# Teensy4_1V3.net
KiCad netlist of a schematic drawn in EAGLE
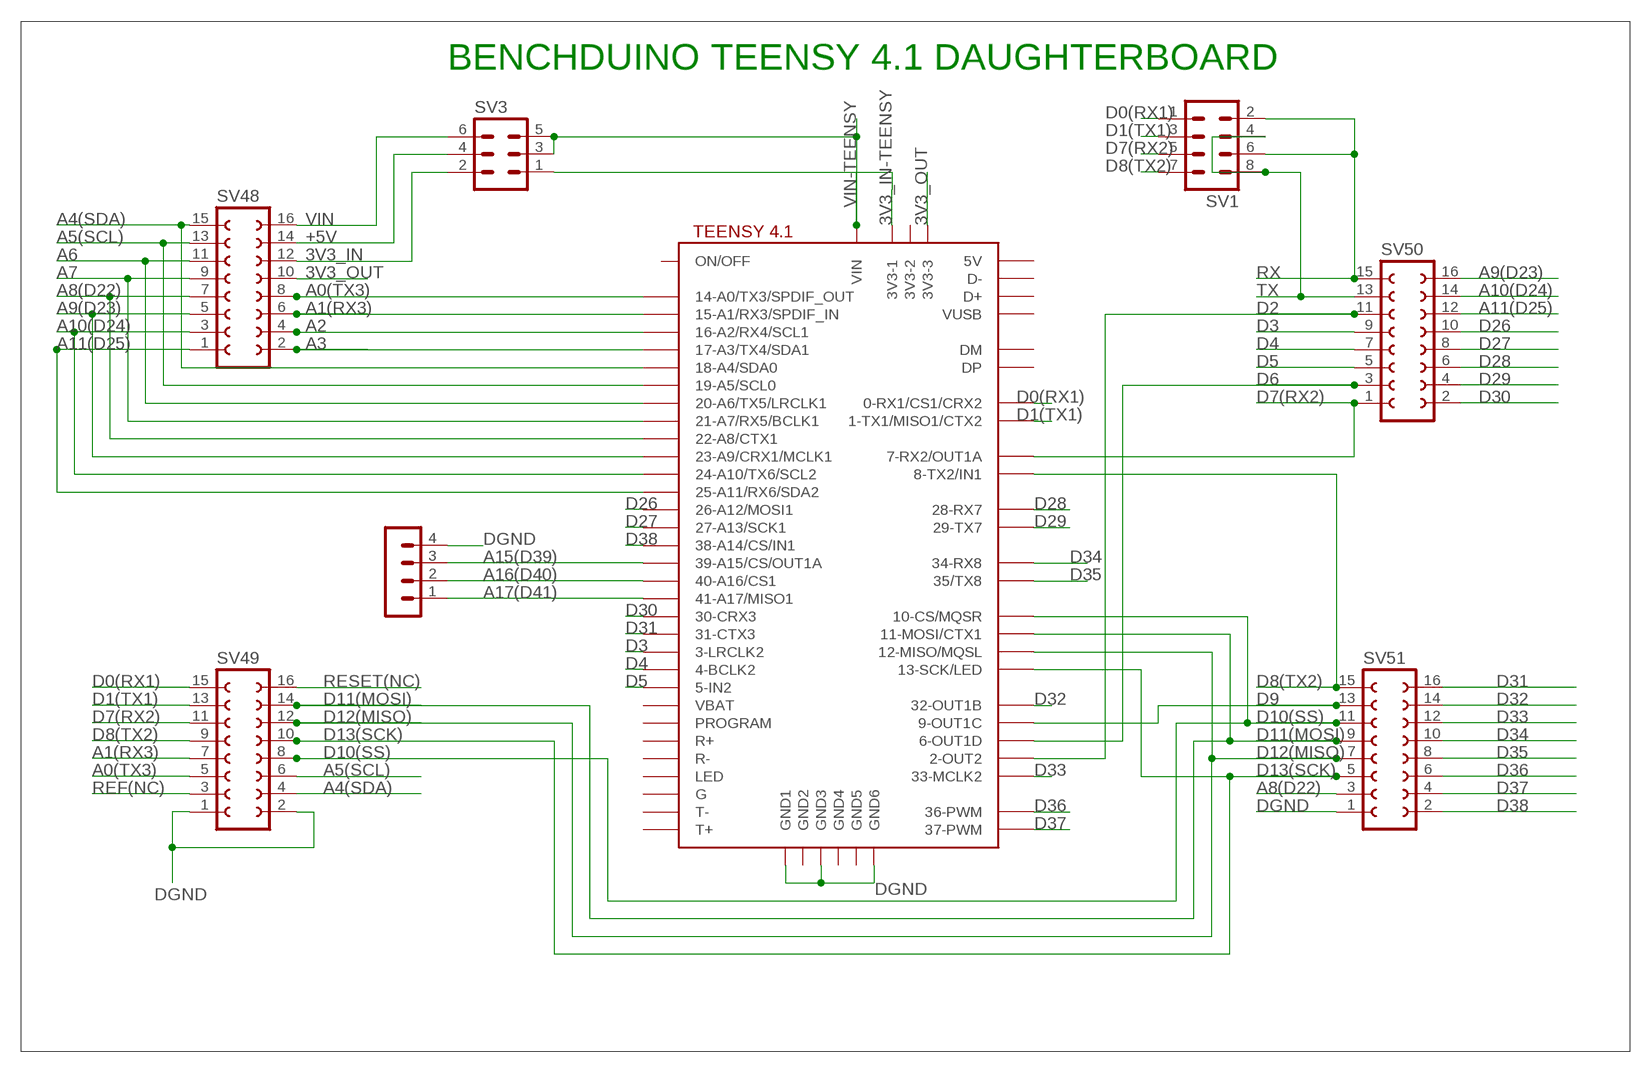
[diagram p0: schematic, sheet 1]

(export (version "E")
  (design (tool "Eeschema 10.0.6"))
  (components
    (comp (ref "SV1")
      (value "MA04-2")
      (footprint "eagle-import:MA04-2")
      (libsource (lib "eagle-import") (part "MA04-2"))
    )
    (comp (ref "SV3")
      (value "MA03-2")
      (footprint "eagle-import:MA03-2")
      (libsource (lib "eagle-import") (part "MA03-2"))
    )
    (comp (ref "SV4")
      (value "MA04-1")
      (footprint "eagle-import:MA04-1")
      (libsource (lib "eagle-import") (part "MA04-1"))
    )
    (comp (ref "SV48")
      (value "FE08-2")
      (footprint "eagle-import:FE08-2")
      (libsource (lib "eagle-import") (part "FE08-2"))
    )
    (comp (ref "SV49")
      (value "FE08-2")
      (footprint "eagle-import:FE08-2")
      (libsource (lib "eagle-import") (part "FE08-2"))
    )
    (comp (ref "SV50")
      (value "FE08-2")
      (footprint "eagle-import:FE08-2")
      (libsource (lib "eagle-import") (part "FE08-2"))
    )
    (comp (ref "SV51")
      (value "FE08-2")
      (footprint "eagle-import:FE08-2")
      (libsource (lib "eagle-import") (part "FE08-2"))
    )
    (comp (ref "U$1")
      (value "TEENSY41")
      (footprint "eagle-import:TEENSY41")
      (libsource (lib "eagle-import") (part "TEENSY41"))
    )
  )
  (nets
    (net (code "1") (name "+5V") (class "Default")
      (node (ref "SV3") (pin "4") (pinfunction "4_4") (pintype "passive"))
      (node (ref "SV48") (pin "14") (pinfunction "14_14") (pintype "passive"))
    )
    (net (code "2") (name "3V3_IN") (class "Default")
      (node (ref "SV3") (pin "2") (pinfunction "2_2") (pintype "passive"))
      (node (ref "SV48") (pin "12") (pinfunction "12_12") (pintype "passive"))
    )
    (net (code "3") (name "3V3_IN-TEENSY") (class "Default")
      (node (ref "SV3") (pin "1") (pinfunction "1_1") (pintype "passive"))
      (node (ref "U$1") (pin "3V3-1") (pinfunction "3V3-1_3V3-1") (pintype "bidirectional"))
    )
    (net (code "4") (name "3V3_OUT") (class "Default")
      (node (ref "SV48") (pin "10") (pinfunction "10_10") (pintype "passive"))
      (node (ref "U$1") (pin "3V3-3") (pinfunction "3V3-3_3V3-3") (pintype "bidirectional"))
    )
    (net (code "5") (name "A0(TX3)") (class "Default")
      (node (ref "SV48") (pin "8") (pinfunction "8_8") (pintype "passive"))
      (node (ref "SV49") (pin "5") (pinfunction "5_5") (pintype "passive"))
      (node (ref "U$1") (pin "14-A0/TX3/SPDIF_OUT") (pinfunction "14-A0/TX3/SPDIF_OUT_14-A0/TX3/SPDIF_OUT") (pintype "bidirectional"))
    )
    (net (code "6") (name "A1(RX3)") (class "Default")
      (node (ref "SV48") (pin "6") (pinfunction "6_6") (pintype "passive"))
      (node (ref "SV49") (pin "7") (pinfunction "7_7") (pintype "passive"))
      (node (ref "U$1") (pin "15-A1/RX3/SPDIF_IN") (pinfunction "15-A1/RX3/SPDIF_IN_15-A1/RX3/SPDIF_IN") (pintype "bidirectional"))
    )
    (net (code "7") (name "A2") (class "Default")
      (node (ref "SV48") (pin "4") (pinfunction "4_4") (pintype "passive"))
      (node (ref "U$1") (pin "16-A2/RX4/SCL1") (pinfunction "16-A2/RX4/SCL1_16-A2/RX4/SCL1") (pintype "bidirectional"))
    )
    (net (code "8") (name "A3") (class "Default")
      (node (ref "SV48") (pin "2") (pinfunction "2_2") (pintype "passive"))
      (node (ref "U$1") (pin "17-A3/TX4/SDA1") (pinfunction "17-A3/TX4/SDA1_17-A3/TX4/SDA1") (pintype "bidirectional"))
    )
    (net (code "9") (name "A4(SDA)") (class "Default")
      (node (ref "SV48") (pin "15") (pinfunction "15_15") (pintype "passive"))
      (node (ref "SV49") (pin "4") (pinfunction "4_4") (pintype "passive"))
      (node (ref "U$1") (pin "18-A4/SDA0") (pinfunction "18-A4/SDA0_18-A4/SDA0") (pintype "bidirectional"))
    )
    (net (code "10") (name "A5(SCL)") (class "Default")
      (node (ref "SV48") (pin "13") (pinfunction "13_13") (pintype "passive"))
      (node (ref "SV49") (pin "6") (pinfunction "6_6") (pintype "passive"))
      (node (ref "U$1") (pin "19-A5/SCL0") (pinfunction "19-A5/SCL0_19-A5/SCL0") (pintype "bidirectional"))
    )
    (net (code "11") (name "A6") (class "Default")
      (node (ref "SV48") (pin "11") (pinfunction "11_11") (pintype "passive"))
      (node (ref "U$1") (pin "20-A6/TX5/LRCLK1") (pinfunction "20-A6/TX5/LRCLK1_20-A6/TX5/LRCLK1") (pintype "bidirectional"))
    )
    (net (code "12") (name "A7") (class "Default")
      (node (ref "SV48") (pin "9") (pinfunction "9_9") (pintype "passive"))
      (node (ref "U$1") (pin "21-A7/RX5/BCLK1") (pinfunction "21-A7/RX5/BCLK1_21-A7/RX5/BCLK1") (pintype "bidirectional"))
    )
    (net (code "13") (name "A8(D22)") (class "Default")
      (node (ref "SV48") (pin "7") (pinfunction "7_7") (pintype "passive"))
      (node (ref "SV51") (pin "3") (pinfunction "3_3") (pintype "passive"))
      (node (ref "U$1") (pin "22-A8/CTX1") (pinfunction "22-A8/CTX1_22-A8/CTX1") (pintype "bidirectional"))
    )
    (net (code "14") (name "A9(D23)") (class "Default")
      (node (ref "SV48") (pin "5") (pinfunction "5_5") (pintype "passive"))
      (node (ref "SV50") (pin "16") (pinfunction "16_16") (pintype "passive"))
      (node (ref "U$1") (pin "23-A9/CRX1/MCLK1") (pinfunction "23-A9/CRX1/MCLK1_23-A9/CRX1/MCLK1") (pintype "bidirectional"))
    )
    (net (code "15") (name "A10(D24)") (class "Default")
      (node (ref "SV48") (pin "3") (pinfunction "3_3") (pintype "passive"))
      (node (ref "SV50") (pin "14") (pinfunction "14_14") (pintype "passive"))
      (node (ref "U$1") (pin "24-A10/TX6/SCL2") (pinfunction "24-A10/TX6/SCL2_24-A10/TX6/SCL2") (pintype "bidirectional"))
    )
    (net (code "16") (name "A11(D25)") (class "Default")
      (node (ref "SV48") (pin "1") (pinfunction "1_1") (pintype "passive"))
      (node (ref "SV50") (pin "12") (pinfunction "12_12") (pintype "passive"))
      (node (ref "U$1") (pin "25-A11/RX6/SDA2") (pinfunction "25-A11/RX6/SDA2_25-A11/RX6/SDA2") (pintype "bidirectional"))
    )
    (net (code "17") (name "A15(D39)") (class "Default")
      (node (ref "SV4") (pin "3") (pinfunction "3_3") (pintype "passive"))
      (node (ref "U$1") (pin "39-A15/CS/OUT1A") (pinfunction "39-A15/CS/OUT1A_39-A15/CS/OUT1A") (pintype "bidirectional"))
    )
    (net (code "18") (name "A16(D40)") (class "Default")
      (node (ref "SV4") (pin "2") (pinfunction "2_2") (pintype "passive"))
      (node (ref "U$1") (pin "40-A16/CS1") (pinfunction "40-A16/CS1_40-A16/CS1") (pintype "bidirectional"))
    )
    (net (code "19") (name "A17(D41)") (class "Default")
      (node (ref "SV4") (pin "1") (pinfunction "1_1") (pintype "passive"))
      (node (ref "U$1") (pin "41-A17/MISO1") (pinfunction "41-A17/MISO1_41-A17/MISO1") (pintype "bidirectional"))
    )
    (net (code "20") (name "D0(RX1)") (class "Default")
      (node (ref "SV1") (pin "1") (pinfunction "1_1") (pintype "passive"))
      (node (ref "SV49") (pin "15") (pinfunction "15_15") (pintype "passive"))
      (node (ref "U$1") (pin "0-RX1/CS1/CRX2") (pinfunction "0-RX1/CS1/CRX2_0-RX1/CS1/CRX2") (pintype "bidirectional"))
    )
    (net (code "21") (name "D1(TX1)") (class "Default")
      (node (ref "SV1") (pin "3") (pinfunction "3_3") (pintype "passive"))
      (node (ref "SV49") (pin "13") (pinfunction "13_13") (pintype "passive"))
      (node (ref "U$1") (pin "1-TX1/MISO1/CTX2") (pinfunction "1-TX1/MISO1/CTX2_1-TX1/MISO1/CTX2") (pintype "bidirectional"))
    )
    (net (code "22") (name "D2") (class "Default")
      (node (ref "SV50") (pin "11") (pinfunction "11_11") (pintype "passive"))
      (node (ref "U$1") (pin "2-OUT2") (pinfunction "2-OUT2_2-OUT2") (pintype "bidirectional"))
    )
    (net (code "23") (name "D3") (class "Default")
      (node (ref "SV50") (pin "9") (pinfunction "9_9") (pintype "passive"))
      (node (ref "U$1") (pin "3-LRCLK2") (pinfunction "3-LRCLK2_3-LRCLK2") (pintype "bidirectional"))
    )
    (net (code "24") (name "D4") (class "Default")
      (node (ref "SV50") (pin "7") (pinfunction "7_7") (pintype "passive"))
      (node (ref "U$1") (pin "4-BCLK2") (pinfunction "4-BCLK2_4-BCLK2") (pintype "bidirectional"))
    )
    (net (code "25") (name "D5") (class "Default")
      (node (ref "SV50") (pin "5") (pinfunction "5_5") (pintype "passive"))
      (node (ref "U$1") (pin "5-IN2") (pinfunction "5-IN2_5-IN2") (pintype "bidirectional"))
    )
    (net (code "26") (name "D6") (class "Default")
      (node (ref "SV50") (pin "3") (pinfunction "3_3") (pintype "passive"))
      (node (ref "U$1") (pin "6-OUT1D") (pinfunction "6-OUT1D_6-OUT1D") (pintype "bidirectional"))
    )
    (net (code "27") (name "D7(RX2)") (class "Default")
      (node (ref "SV1") (pin "5") (pinfunction "5_5") (pintype "passive"))
      (node (ref "SV49") (pin "11") (pinfunction "11_11") (pintype "passive"))
      (node (ref "SV50") (pin "1") (pinfunction "1_1") (pintype "passive"))
      (node (ref "U$1") (pin "7-RX2/OUT1A") (pinfunction "7-RX2/OUT1A_7-RX2/OUT1A") (pintype "bidirectional"))
    )
    (net (code "28") (name "D8(TX2)") (class "Default")
      (node (ref "SV1") (pin "7") (pinfunction "7_7") (pintype "passive"))
      (node (ref "SV49") (pin "9") (pinfunction "9_9") (pintype "passive"))
      (node (ref "SV51") (pin "15") (pinfunction "15_15") (pintype "passive"))
      (node (ref "U$1") (pin "8-TX2/IN2") (pinfunction "8-TX2/IN1_8-TX2/IN2") (pintype "bidirectional"))
    )
    (net (code "29") (name "D9") (class "Default")
      (node (ref "SV51") (pin "13") (pinfunction "13_13") (pintype "passive"))
      (node (ref "U$1") (pin "9-OUT1C") (pinfunction "9-OUT1C_9-OUT1C") (pintype "bidirectional"))
    )
    (net (code "30") (name "D10(SS)") (class "Default")
      (node (ref "SV49") (pin "8") (pinfunction "8_8") (pintype "passive"))
      (node (ref "SV51") (pin "11") (pinfunction "11_11") (pintype "passive"))
      (node (ref "U$1") (pin "10-CS\\MQSR") (pinfunction "10-CS/MQSR_10-CS\\MQSR") (pintype "bidirectional"))
    )
    (net (code "31") (name "D11(MOSI)") (class "Default")
      (node (ref "SV49") (pin "14") (pinfunction "14_14") (pintype "passive"))
      (node (ref "SV51") (pin "9") (pinfunction "9_9") (pintype "passive"))
      (node (ref "U$1") (pin "11-MOSI/CTX1") (pinfunction "11-MOSI/CTX1_11-MOSI/CTX1") (pintype "bidirectional"))
    )
    (net (code "32") (name "D12(MISO)") (class "Default")
      (node (ref "SV49") (pin "12") (pinfunction "12_12") (pintype "passive"))
      (node (ref "SV51") (pin "7") (pinfunction "7_7") (pintype "passive"))
      (node (ref "U$1") (pin "12-MISO/MQSL") (pinfunction "12-MISO/MQSL_12-MISO/MQSL") (pintype "bidirectional"))
    )
    (net (code "33") (name "D13(SCK)") (class "Default")
      (node (ref "SV49") (pin "10") (pinfunction "10_10") (pintype "passive"))
      (node (ref "SV51") (pin "5") (pinfunction "5_5") (pintype "passive"))
      (node (ref "U$1") (pin "13-SCK/LED") (pinfunction "13-SCK/LED_13-SCK/LED") (pintype "bidirectional"))
    )
    (net (code "34") (name "D26") (class "Default")
      (node (ref "SV50") (pin "10") (pinfunction "10_10") (pintype "passive"))
      (node (ref "U$1") (pin "26-A12/MOSI1") (pinfunction "26-A12/MOSI1_26-A12/MOSI1") (pintype "bidirectional"))
    )
    (net (code "35") (name "D27") (class "Default")
      (node (ref "SV50") (pin "8") (pinfunction "8_8") (pintype "passive"))
      (node (ref "U$1") (pin "27-A13/SCK1") (pinfunction "27-A13/SCK1_27-A13/SCK1") (pintype "bidirectional"))
    )
    (net (code "36") (name "D28") (class "Default")
      (node (ref "SV50") (pin "6") (pinfunction "6_6") (pintype "passive"))
      (node (ref "U$1") (pin "28-RX7") (pinfunction "28-RX7_28-RX7") (pintype "bidirectional"))
    )
    (net (code "37") (name "D29") (class "Default")
      (node (ref "SV50") (pin "4") (pinfunction "4_4") (pintype "passive"))
      (node (ref "U$1") (pin "29-TX7") (pinfunction "29-TX7_29-TX7") (pintype "bidirectional"))
    )
    (net (code "38") (name "D30") (class "Default")
      (node (ref "SV50") (pin "2") (pinfunction "2_2") (pintype "passive"))
      (node (ref "U$1") (pin "30-CRX3") (pinfunction "30-CRX3_30-CRX3") (pintype "bidirectional"))
    )
    (net (code "39") (name "D31") (class "Default")
      (node (ref "SV51") (pin "16") (pinfunction "16_16") (pintype "passive"))
      (node (ref "U$1") (pin "31-CTX3") (pinfunction "31-CTX3_31-CTX3") (pintype "bidirectional"))
    )
    (net (code "40") (name "D32") (class "Default")
      (node (ref "SV51") (pin "14") (pinfunction "14_14") (pintype "passive"))
      (node (ref "U$1") (pin "32-OUT1B") (pinfunction "32-OUT1B_32-OUT1B") (pintype "bidirectional"))
    )
    (net (code "41") (name "D33") (class "Default")
      (node (ref "SV51") (pin "12") (pinfunction "12_12") (pintype "passive"))
      (node (ref "U$1") (pin "33-MCLK2") (pinfunction "33-MCLK2_33-MCLK2") (pintype "bidirectional"))
    )
    (net (code "42") (name "D34") (class "Default")
      (node (ref "SV51") (pin "10") (pinfunction "10_10") (pintype "passive"))
      (node (ref "U$1") (pin "34-RX8") (pinfunction "34-RX8_34-RX8") (pintype "bidirectional"))
    )
    (net (code "43") (name "D35") (class "Default")
      (node (ref "SV51") (pin "8") (pinfunction "8_8") (pintype "passive"))
      (node (ref "U$1") (pin "35-TX8") (pinfunction "35/TX8_35-TX8") (pintype "bidirectional"))
    )
    (net (code "44") (name "D36") (class "Default")
      (node (ref "SV51") (pin "6") (pinfunction "6_6") (pintype "passive"))
      (node (ref "U$1") (pin "36-PWM") (pinfunction "36-PWM_36-PWM") (pintype "bidirectional"))
    )
    (net (code "45") (name "D37") (class "Default")
      (node (ref "SV51") (pin "4") (pinfunction "4_4") (pintype "passive"))
      (node (ref "U$1") (pin "37-PWM") (pinfunction "37-PWM_37-PWM") (pintype "bidirectional"))
    )
    (net (code "46") (name "D38") (class "Default")
      (node (ref "SV51") (pin "2") (pinfunction "2_2") (pintype "passive"))
      (node (ref "U$1") (pin "38-A14/CS/IN1") (pinfunction "38-A14/CS/IN1_38-A14/CS/IN1") (pintype "bidirectional"))
    )
    (net (code "47") (name "DGND") (class "Default")
      (node (ref "SV4") (pin "4") (pinfunction "4_4") (pintype "passive"))
      (node (ref "SV49") (pin "1") (pinfunction "1_1") (pintype "passive"))
      (node (ref "SV49") (pin "2") (pinfunction "2_2") (pintype "passive"))
      (node (ref "SV51") (pin "1") (pinfunction "1_1") (pintype "passive"))
      (node (ref "U$1") (pin "GND1") (pinfunction "GND1_GND1") (pintype "bidirectional"))
      (node (ref "U$1") (pin "GND3") (pinfunction "GND3_GND3") (pintype "bidirectional"))
      (node (ref "U$1") (pin "GND6") (pinfunction "GND6_GND6") (pintype "bidirectional"))
    )
    (net (code "48") (name "REF(NC)") (class "Default")
      (node (ref "SV49") (pin "3") (pinfunction "3_3") (pintype "passive"))
    )
    (net (code "49") (name "RESET(NC)") (class "Default")
      (node (ref "SV49") (pin "16") (pinfunction "16_16") (pintype "passive"))
    )
    (net (code "50") (name "RX") (class "Default")
      (node (ref "SV1") (pin "2") (pinfunction "2_2") (pintype "passive"))
      (node (ref "SV1") (pin "6") (pinfunction "6_6") (pintype "passive"))
      (node (ref "SV50") (pin "15") (pinfunction "15_15") (pintype "passive"))
    )
    (net (code "51") (name "TX") (class "Default")
      (node (ref "SV1") (pin "4") (pinfunction "4_4") (pintype "passive"))
      (node (ref "SV1") (pin "8") (pinfunction "8_8") (pintype "passive"))
      (node (ref "SV50") (pin "13") (pinfunction "13_13") (pintype "passive"))
    )
    (net (code "52") (name "VIN") (class "Default")
      (node (ref "SV3") (pin "6") (pinfunction "6_6") (pintype "passive"))
      (node (ref "SV48") (pin "16") (pinfunction "16_16") (pintype "passive"))
    )
    (net (code "53") (name "VIN-TEENSY") (class "Default")
      (node (ref "SV3") (pin "3") (pinfunction "3_3") (pintype "passive"))
      (node (ref "SV3") (pin "5") (pinfunction "5_5") (pintype "passive"))
      (node (ref "U$1") (pin "VIN") (pinfunction "VIN_VIN") (pintype "bidirectional"))
    )
    (net (code "54") (name "unconnected-(U$1-5V-Pad+5V)") (class "Default")
      (node (ref "U$1") (pin "+5V") (pinfunction "5V_+5V") (pintype "bidirectional"))
    )
    (net (code "55") (name "unconnected-(U$1-Pad3V3-2)") (class "Default")
      (node (ref "U$1") (pin "3V3-2") (pinfunction "3V3-2_3V3-2") (pintype "bidirectional"))
    )
    (net (code "56") (name "unconnected-(U$1-PadD+)") (class "Default")
      (node (ref "U$1") (pin "D+") (pinfunction "D+_D+") (pintype "bidirectional"))
    )
    (net (code "57") (name "unconnected-(U$1-PadD-)") (class "Default")
      (node (ref "U$1") (pin "D-") (pinfunction "D-_D-") (pintype "bidirectional"))
    )
    (net (code "58") (name "unconnected-(U$1-PadDM)") (class "Default")
      (node (ref "U$1") (pin "DM") (pinfunction "DM_DM") (pintype "bidirectional"))
    )
    (net (code "59") (name "unconnected-(U$1-PadDP)") (class "Default")
      (node (ref "U$1") (pin "DP") (pinfunction "DP_DP") (pintype "bidirectional"))
    )
    (net (code "60") (name "unconnected-(U$1-PadG)") (class "Default")
      (node (ref "U$1") (pin "G") (pinfunction "G_G") (pintype "bidirectional"))
    )
    (net (code "61") (name "unconnected-(U$1-PadGND2)") (class "Default")
      (node (ref "U$1") (pin "GND2") (pinfunction "GND2_GND2") (pintype "bidirectional"))
    )
    (net (code "62") (name "unconnected-(U$1-PadGND4)") (class "Default")
      (node (ref "U$1") (pin "GND4") (pinfunction "GND4_GND4") (pintype "bidirectional"))
    )
    (net (code "63") (name "unconnected-(U$1-PadGND5)") (class "Default")
      (node (ref "U$1") (pin "GND5") (pinfunction "GND5_GND5") (pintype "bidirectional"))
    )
    (net (code "64") (name "unconnected-(U$1-PadLED)") (class "Default")
      (node (ref "U$1") (pin "LED") (pinfunction "LED_LED") (pintype "bidirectional"))
    )
    (net (code "65") (name "unconnected-(U$1-PadON{slash}OFF)") (class "Default")
      (node (ref "U$1") (pin "ON/OFF") (pinfunction "ON/OFF_ON/OFF") (pintype "bidirectional"))
    )
    (net (code "66") (name "unconnected-(U$1-PadPROGRAM)") (class "Default")
      (node (ref "U$1") (pin "PROGRAM") (pinfunction "PROGRAM_PROGRAM") (pintype "bidirectional"))
    )
    (net (code "67") (name "unconnected-(U$1-PadR+)") (class "Default")
      (node (ref "U$1") (pin "R+") (pinfunction "R+_R+") (pintype "bidirectional"))
    )
    (net (code "68") (name "unconnected-(U$1-PadR-)") (class "Default")
      (node (ref "U$1") (pin "R-") (pinfunction "R-_R-") (pintype "bidirectional"))
    )
    (net (code "69") (name "unconnected-(U$1-PadT+)") (class "Default")
      (node (ref "U$1") (pin "T+") (pinfunction "T+_T+") (pintype "bidirectional"))
    )
    (net (code "70") (name "unconnected-(U$1-PadT-)") (class "Default")
      (node (ref "U$1") (pin "T-") (pinfunction "T-_T-") (pintype "bidirectional"))
    )
    (net (code "71") (name "unconnected-(U$1-PadVBAT)") (class "Default")
      (node (ref "U$1") (pin "VBAT") (pinfunction "VBAT_VBAT") (pintype "bidirectional"))
    )
    (net (code "72") (name "unconnected-(U$1-PadVUSB)") (class "Default")
      (node (ref "U$1") (pin "VUSB") (pinfunction "VUSB_VUSB") (pintype "bidirectional"))
    )
  )
)
